# Schematic_IOT_Mertz.net
KiCad netlist of a schematic drawn in EasyEDA
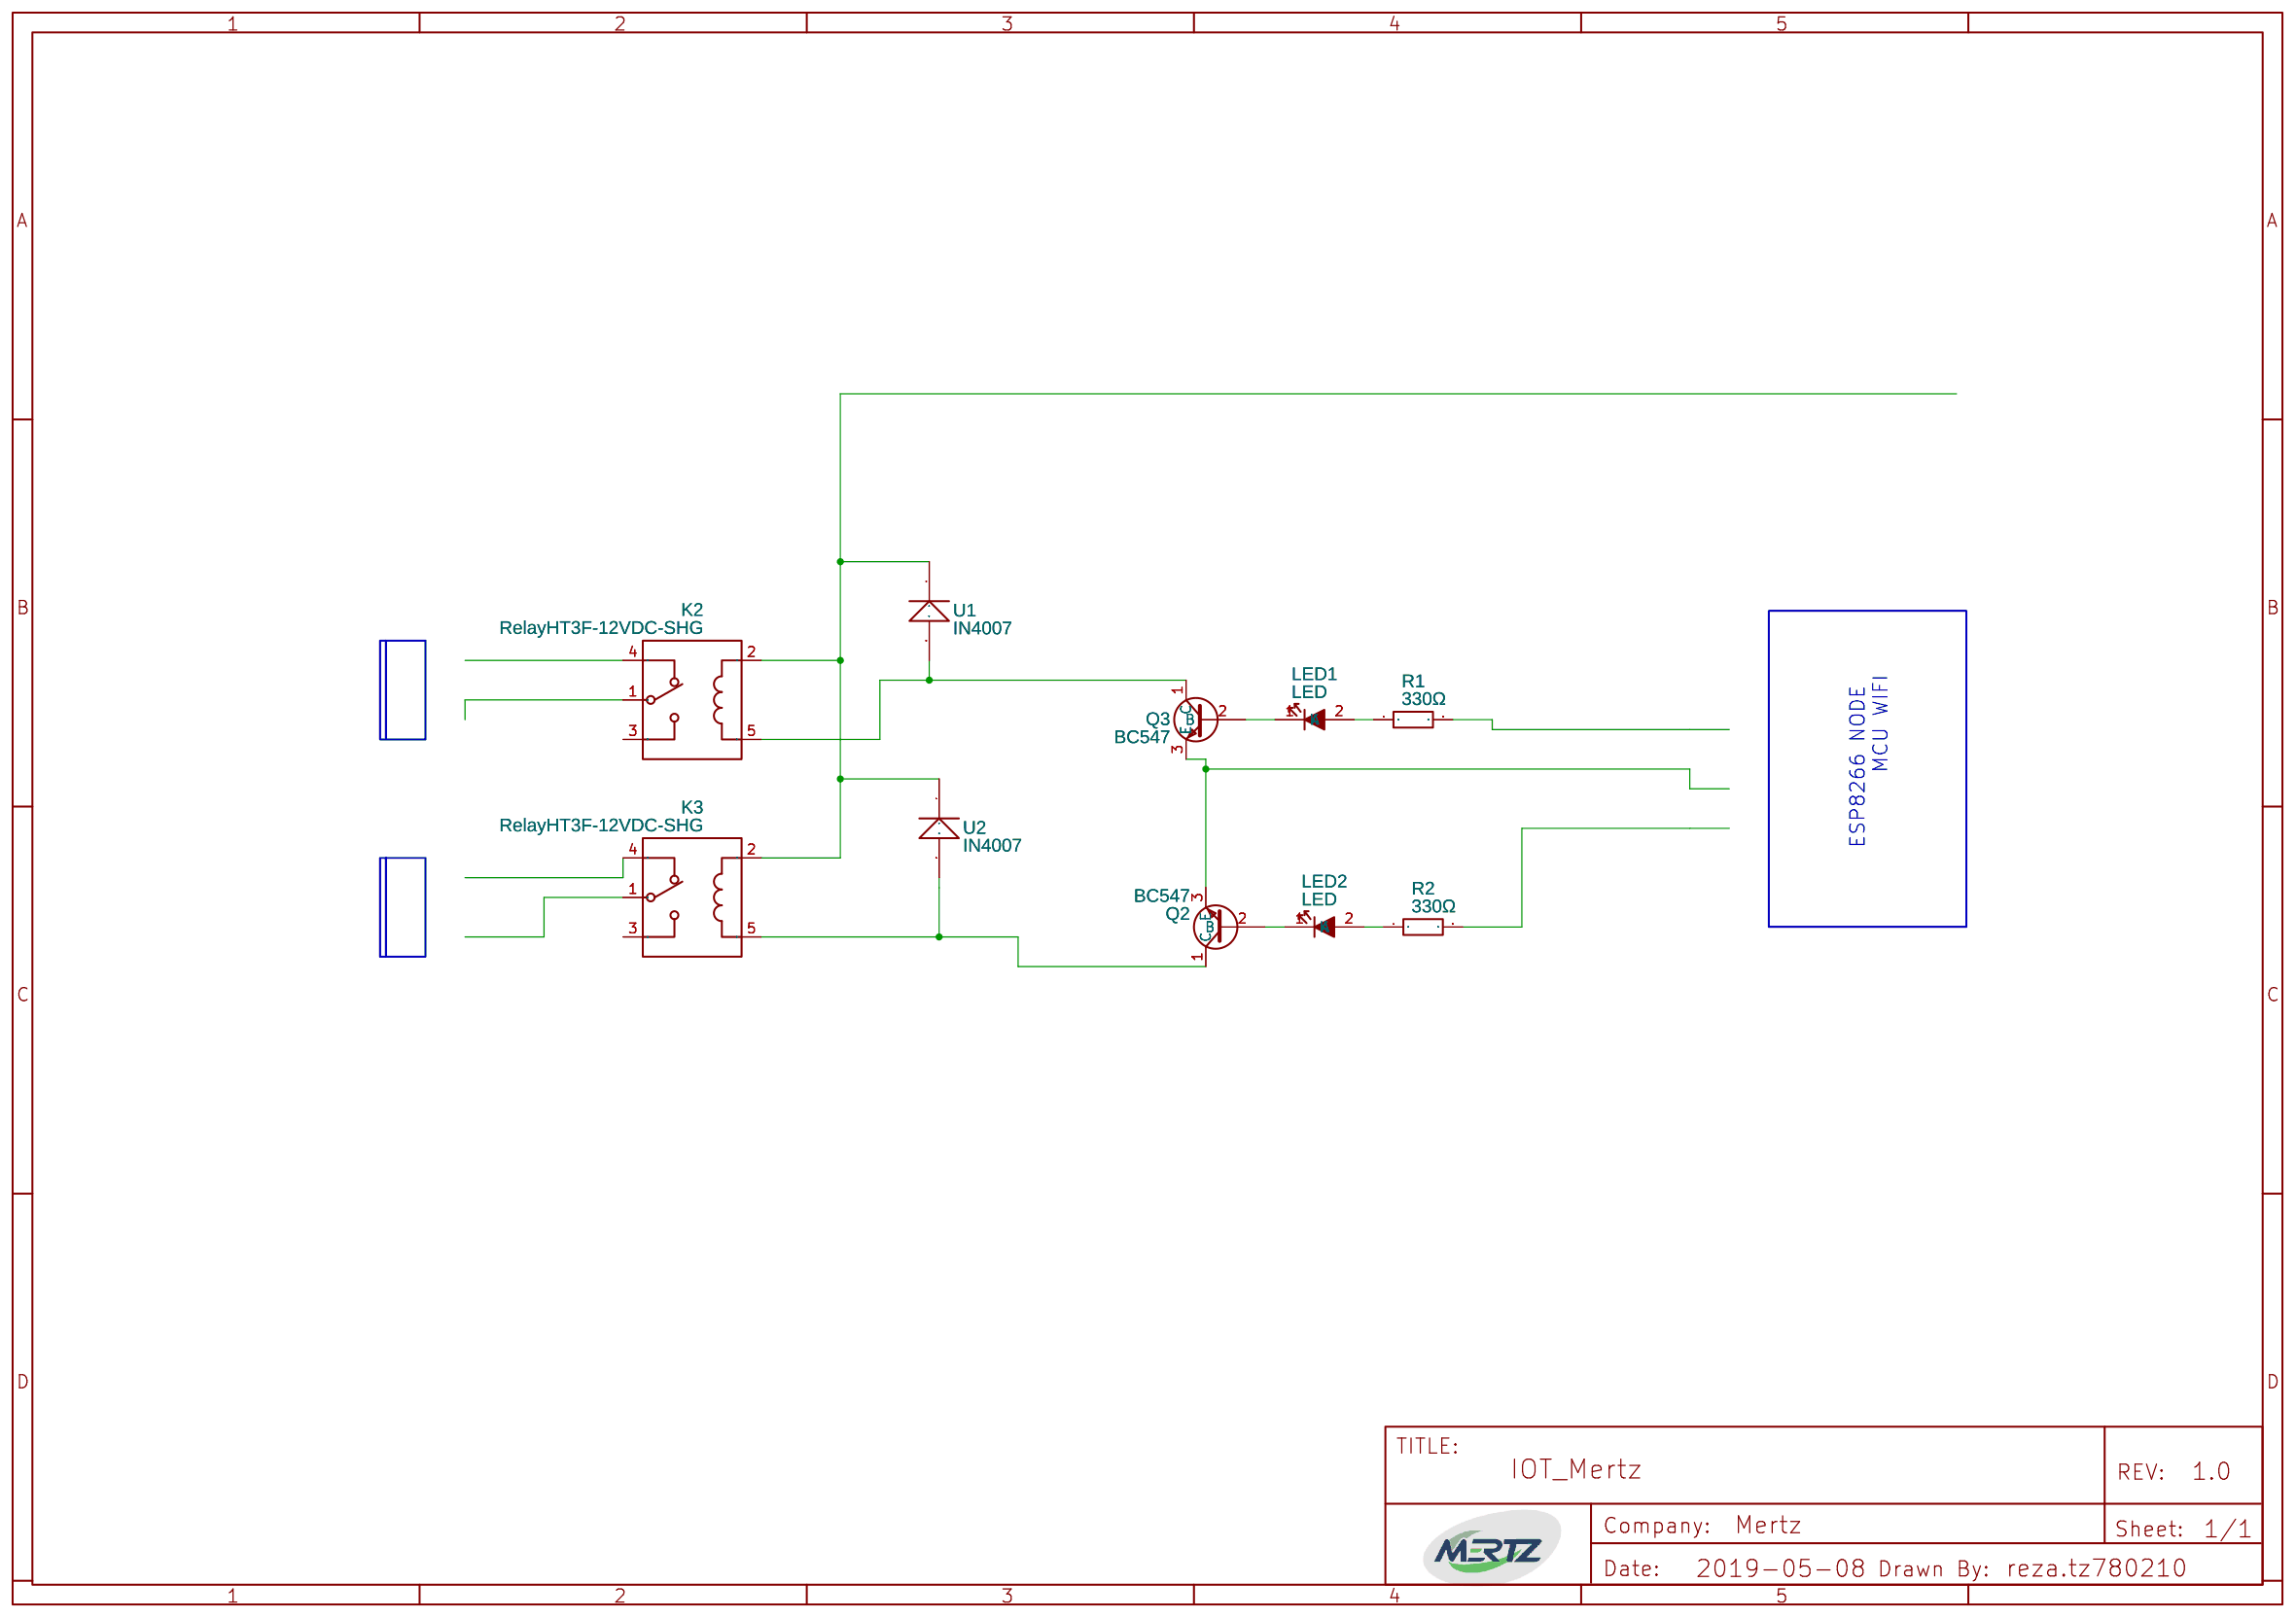
[diagram p0: schematic sheet]

(export (version "E")
  (design (tool "Eeschema 10.0.6"))
  (components
    (comp (ref "K2")
      (value "RelayHT3F-12VDC-SHG")
      (fields (field (name "BOM_Supplier Part") "C22022"))
      (libsource (lib "") (part "Unknown_295_275"))
    )
    (comp (ref "K3")
      (value "RelayHT3F-12VDC-SHG")
      (fields (field (name "BOM_Supplier Part") "C22022"))
      (libsource (lib "") (part "Unknown_295_375"))
    )
    (comp (ref "LED1")
      (value "LED")
      (fields (field (name "BOM_Manufacturer Part") "?"))
      (libsource (lib "") (part "Unknown_615_285"))
    )
    (comp (ref "LED2")
      (value "LED")
      (fields (field (name "BOM_Manufacturer Part") "?"))
      (libsource (lib "") (part "Unknown_620_390"))
    )
    (comp (ref "Q2")
      (value "BC547")
      (fields (field (name "BOM_Manufacturer Part") "?"))
      (libsource (lib "") (part "Unknown_570_390"))
    )
    (comp (ref "Q3")
      (value "BC547")
      (fields (field (name "BOM_Manufacturer Part") "?"))
      (libsource (lib "") (part "Unknown_560_285"))
    )
    (comp (ref "R1")
      (value "330Ω")
      (fields
        (field (name "BOM_Manufacturer Part") "1206W4F3300T5E")
        (field (name "BOM_Supplier Part") "C17930")
      )
      (libsource (lib "") (part "Unknown_665_285"))
    )
    (comp (ref "R2")
      (value "330Ω")
      (fields
        (field (name "BOM_Manufacturer Part") "1206W4F3300T5E")
        (field (name "BOM_Supplier Part") "C17930")
      )
      (libsource (lib "") (part "Unknown_670_390"))
    )
    (comp (ref "U1") (value "IN4007") (libsource (lib "") (part "Unknown_420_225")))
    (comp (ref "U2") (value "IN4007") (libsource (lib "") (part "Unknown_425_335")))
  )
  (nets
    (net (code "1") (name "Net-(K2-Pad2)") (class "Default")
      (node (ref "K2") (pin "2") (pinfunction "2_2") (pintype "unspecified"))
      (node (ref "K3") (pin "2") (pinfunction "2_2") (pintype "unspecified"))
      (node (ref "U1") (pin "1") (pinfunction "1_1") (pintype "unspecified"))
      (node (ref "U2") (pin "1") (pinfunction "1_1") (pintype "unspecified"))
    )
    (net (code "2") (name "Net-(LED1-A)") (class "Default")
      (node (ref "LED1") (pin "2") (pinfunction "A_2") (pintype "unspecified"))
      (node (ref "R1") (pin "1") (pinfunction "1_1") (pintype "input"))
    )
    (net (code "3") (name "Net-(LED1-K)") (class "Default")
      (node (ref "LED1") (pin "1") (pinfunction "K_1") (pintype "unspecified"))
      (node (ref "Q3") (pin "2") (pinfunction "B_2") (pintype "input"))
    )
    (net (code "4") (name "Net-(LED2-A)") (class "Default")
      (node (ref "LED2") (pin "2") (pinfunction "A_2") (pintype "unspecified"))
      (node (ref "R2") (pin "1") (pinfunction "1_1") (pintype "input"))
    )
    (net (code "5") (name "Net-(LED2-K)") (class "Default")
      (node (ref "LED2") (pin "1") (pinfunction "K_1") (pintype "unspecified"))
      (node (ref "Q2") (pin "2") (pinfunction "B_2") (pintype "input"))
    )
    (net (code "6") (name "Net-(Q2-C)") (class "Default")
      (node (ref "K3") (pin "5") (pinfunction "5_5") (pintype "unspecified"))
      (node (ref "Q2") (pin "1") (pinfunction "C_1") (pintype "unspecified"))
      (node (ref "U2") (pin "2") (pinfunction "2_2") (pintype "unspecified"))
    )
    (net (code "7") (name "Net-(Q2-E)") (class "Default")
      (node (ref "Q2") (pin "3") (pinfunction "E_3") (pintype "unspecified"))
      (node (ref "Q3") (pin "3") (pinfunction "E_3") (pintype "unspecified"))
    )
    (net (code "8") (name "Net-(Q3-C)") (class "Default")
      (node (ref "K2") (pin "5") (pinfunction "5_5") (pintype "unspecified"))
      (node (ref "Q3") (pin "1") (pinfunction "C_1") (pintype "unspecified"))
      (node (ref "U1") (pin "2") (pinfunction "2_2") (pintype "unspecified"))
    )
    (net (code "9") (name "unconnected-(K2-Pad1)") (class "Default")
      (node (ref "K2") (pin "1") (pinfunction "1_1") (pintype "unspecified"))
    )
    (net (code "10") (name "unconnected-(K2-Pad3)") (class "Default")
      (node (ref "K2") (pin "3") (pinfunction "3_3") (pintype "unspecified"))
    )
    (net (code "11") (name "unconnected-(K2-Pad4)") (class "Default")
      (node (ref "K2") (pin "4") (pinfunction "4_4") (pintype "unspecified"))
    )
    (net (code "12") (name "unconnected-(K3-Pad1)") (class "Default")
      (node (ref "K3") (pin "1") (pinfunction "1_1") (pintype "unspecified"))
    )
    (net (code "13") (name "unconnected-(K3-Pad3)") (class "Default")
      (node (ref "K3") (pin "3") (pinfunction "3_3") (pintype "unspecified"))
    )
    (net (code "14") (name "unconnected-(K3-Pad4)") (class "Default")
      (node (ref "K3") (pin "4") (pinfunction "4_4") (pintype "unspecified"))
    )
    (net (code "15") (name "unconnected-(R1-Pad2)") (class "Default")
      (node (ref "R1") (pin "2") (pinfunction "2_2") (pintype "input"))
    )
    (net (code "16") (name "unconnected-(R2-Pad2)") (class "Default")
      (node (ref "R2") (pin "2") (pinfunction "2_2") (pintype "input"))
    )
  )
)
